# 20240925.net
KiCad netlist of a schematic drawn in Altium Designer
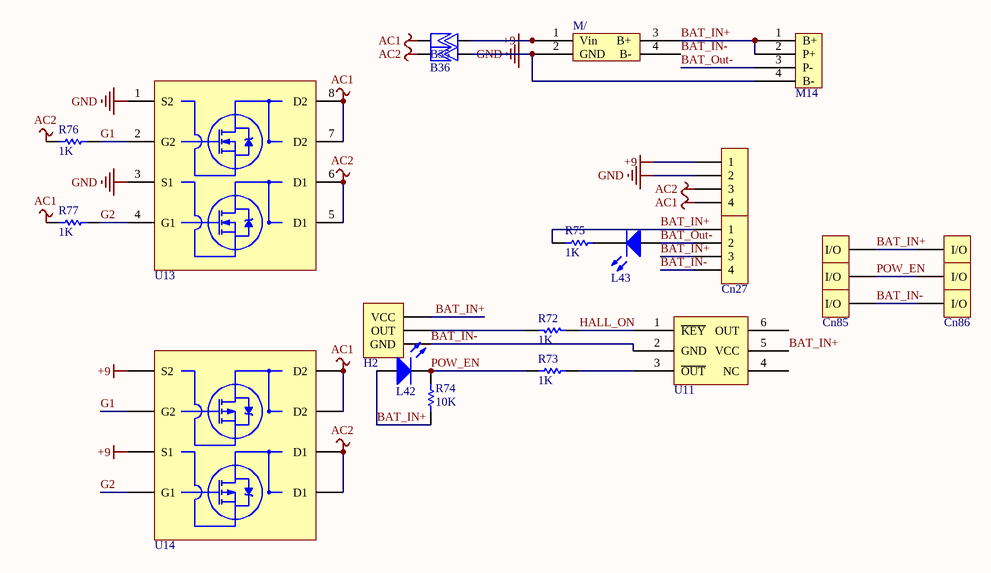
[diagram p0: 磁開關電路_20240925.SchDoc]

(export (version "E")
  (design (tool "Eeschema 10.0.6"))
  (components
    (comp (ref "B35")
      (value "短路")
      (footprint "BYPASS-1206")
      (description "短路焊點(如標註短路則需額外補錫使其短路)")
      (libsource (lib "MyLibray") (part "Bypass"))
    )
    (comp (ref "B36")
      (value "短路")
      (footprint "BYPASS-1206")
      (description "短路焊點(如標註短路則需額外補錫使其短路)")
      (libsource (lib "MyLibray") (part "Bypass"))
    )
    (comp (ref "Cn22")
      (value "KF2510-4")
      (footprint "Connector_KF2510-4W")
      (description "接線端子")
      (libsource (lib "MyLibray") (part "Contact(4P)"))
    )
    (comp (ref "Cn27")
      (value "KF2510-4")
      (footprint "Connector_KF2510-4W")
      (description "接線端子")
      (libsource (lib "MyLibray") (part "Contact(4P)"))
    )
    (comp (ref "Cn81")
      (value "Contact")
      (footprint "Contact_Joints1*0.5")
      (description "接線端子、接點、郵票孔(非焊接元件)")
      (libsource (lib "") (part "Contact_1"))
    )
    (comp (ref "Cn82")
      (value "Contact")
      (footprint "Contact_Joints1*0.5")
      (description "接線端子、接點、郵票孔(非焊接元件)")
      (libsource (lib "MyLibray") (part "Contact"))
    )
    (comp (ref "Cn83")
      (value "Contact")
      (footprint "Contact_Joints1*0.5")
      (description "接線端子、接點、郵票孔(非焊接元件)")
      (libsource (lib "") (part "Contact_1"))
    )
    (comp (ref "Cn84")
      (value "Contact")
      (footprint "Contact_Joints1*0.5")
      (description "接線端子、接點、郵票孔(非焊接元件)")
      (libsource (lib "MyLibray") (part "Contact"))
    )
    (comp (ref "Cn85")
      (value "Contact")
      (footprint "Contact_Joints1*0.5")
      (description "接線端子、接點、郵票孔(非焊接元件)")
      (libsource (lib "") (part "Contact_1"))
    )
    (comp (ref "Cn86")
      (value "Contact")
      (footprint "Contact_Joints1*0.5")
      (description "接線端子、接點、郵票孔(非焊接元件)")
      (libsource (lib "MyLibray") (part "Contact"))
    )
    (comp (ref "H2")
      (value "A3212")
      (footprint "SOT 23-3")
      (description "感測器_霍爾")
      (libsource (lib "MyLibray") (part "Sensor_Hall"))
    )
    (comp (ref "L42")
      (value "藍")
      (footprint "LED-1206")
      (description "LED")
      (libsource (lib "MyLibray") (part "LED"))
    )
    (comp (ref "L43")
      (value "藍")
      (footprint "LED-1206")
      (description "LED")
      (libsource (lib "MyLibray") (part "LED"))
    )
    (comp (ref "M/")
      (value "4056H+DW01A_Module")
      (footprint "4056H+DW01A_Module")
      (description "鋰電池充電保護板")
      (libsource (lib "MyLibray") (part "4056H+DW01A_Module"))
    )
    (comp (ref "M14")
      (value "Module_DW01A")
      (footprint "DW01A_Module")
      (description "鋰電池保護版")
      (libsource (lib "MyLibray") (part "Module_DW01A"))
    )
    (comp (ref "R72")
      (value "1K")
      (footprint "Res-1206")
      (description "電阻")
      (libsource (lib "MyLibray") (part "Res"))
    )
    (comp (ref "R73")
      (value "1K")
      (footprint "Res-1206")
      (description "電阻")
      (libsource (lib "MyLibray") (part "Res"))
    )
    (comp (ref "R74")
      (value "10K")
      (footprint "Res_1/4")
      (description "電阻")
      (libsource (lib "MyLibray") (part "Res"))
    )
    (comp (ref "R75")
      (value "1K")
      (footprint "Res-1206")
      (description "電阻")
      (libsource (lib "MyLibray") (part "Res"))
    )
    (comp (ref "R76")
      (value "1K")
      (footprint "Res-1206")
      (description "電阻")
      (libsource (lib "MyLibray") (part "Res"))
    )
    (comp (ref "R77")
      (value "1K")
      (footprint "Res-1206")
      (description "電阻")
      (libsource (lib "MyLibray") (part "Res"))
    )
    (comp (ref "U11")
      (value "CS2130")
      (footprint "SOT 23-6")
      (description "單鍵ON/OFF芯片")
      (libsource (lib "MyLibray") (part "CS2130"))
    )
    (comp (ref "U13")
      (value "AO4800")
      (footprint "SOP-8")
      (description "MOS,雙NMOS")
      (libsource (lib "MyLibray") (part "MOS_Dual N_AO4800"))
    )
    (comp (ref "U14")
      (value "AO4801")
      (footprint "SOP-8")
      (description "MOS,雙PMOS")
      (libsource (lib "MyLibray") (part "MOS_Dual P_AO4801"))
    )
  )
  (nets
    (net (code "1") (name "+9") (class "Default")
      (node (ref "B35") (pin "2") (pinfunction "2_2") (pintype "passive"))
      (node (ref "Cn22") (pin "1") (pinfunction "1_1") (pintype "passive"))
      (node (ref "M/") (pin "1") (pinfunction "Vin_1") (pintype "passive"))
      (node (ref "U14") (pin "1") (pinfunction "S2_1") (pintype "passive"))
      (node (ref "U14") (pin "3") (pinfunction "S1_3") (pintype "passive"))
    )
    (net (code "2") (name "/BAT_IN+") (class "Default")
      (node (ref "Cn27") (pin "1") (pinfunction "1_1") (pintype "passive"))
      (node (ref "Cn27") (pin "3") (pinfunction "3_3") (pintype "passive"))
      (node (ref "Cn81") (pin "1") (pinfunction "I/O_1") (pintype "passive"))
      (node (ref "Cn82") (pin "1") (pinfunction "I/O_1") (pintype "passive"))
      (node (ref "H2") (pin "1") (pinfunction "VCC_1") (pintype "power_in"))
      (node (ref "L42") (pin "2") (pinfunction "A_2") (pintype "passive"))
      (node (ref "M/") (pin "3") (pinfunction "B+_3") (pintype "passive"))
      (node (ref "M14") (pin "1") (pinfunction "B+_1") (pintype "passive"))
      (node (ref "M14") (pin "2") (pinfunction "P+_2") (pintype "passive"))
      (node (ref "R74") (pin "2") (pinfunction "2_2") (pintype "passive"))
      (node (ref "R75") (pin "2") (pinfunction "2_2") (pintype "passive"))
      (node (ref "U11") (pin "5") (pinfunction "VCC_5") (pintype "passive"))
    )
    (net (code "3") (name "/BAT_IN-") (class "Default")
      (node (ref "Cn27") (pin "4") (pinfunction "4_4") (pintype "passive"))
      (node (ref "Cn85") (pin "1") (pinfunction "I/O_1") (pintype "passive"))
      (node (ref "Cn86") (pin "1") (pinfunction "I/O_1") (pintype "passive"))
      (node (ref "H2") (pin "3") (pinfunction "GND_3") (pintype "power_in"))
      (node (ref "M/") (pin "4") (pinfunction "B-_4") (pintype "passive"))
      (node (ref "U11") (pin "2") (pinfunction "GND_2") (pintype "passive"))
    )
    (net (code "4") (name "/BAT_Out-") (class "Default")
      (node (ref "Cn27") (pin "2") (pinfunction "2_2") (pintype "passive"))
      (node (ref "L43") (pin "2") (pinfunction "A_2") (pintype "passive"))
      (node (ref "M14") (pin "3") (pinfunction "P-_3") (pintype "passive"))
    )
    (net (code "5") (name "/G1") (class "Default")
      (node (ref "R76") (pin "1") (pinfunction "1_1") (pintype "passive"))
      (node (ref "U13") (pin "2") (pinfunction "G2_2") (pintype "passive"))
      (node (ref "U14") (pin "2") (pinfunction "G2_2") (pintype "passive"))
    )
    (net (code "6") (name "/G2") (class "Default")
      (node (ref "R77") (pin "1") (pinfunction "1_1") (pintype "passive"))
      (node (ref "U13") (pin "4") (pinfunction "G1_4") (pintype "passive"))
      (node (ref "U14") (pin "4") (pinfunction "G1_4") (pintype "passive"))
    )
    (net (code "7") (name "/HALL_ON") (class "Default")
      (node (ref "R72") (pin "1") (pinfunction "1_1") (pintype "passive"))
      (node (ref "U11") (pin "1") (pinfunction "~{KEY}_1") (pintype "passive"))
    )
    (net (code "8") (name "/POW_EN") (class "Default")
      (node (ref "Cn83") (pin "1") (pinfunction "I/O_1") (pintype "passive"))
      (node (ref "Cn84") (pin "1") (pinfunction "I/O_1") (pintype "passive"))
      (node (ref "L42") (pin "1") (pinfunction "K_1") (pintype "passive"))
      (node (ref "R73") (pin "1") (pinfunction "1_1") (pintype "passive"))
      (node (ref "R74") (pin "1") (pinfunction "1_1") (pintype "passive"))
    )
    (net (code "9") (name "AC1") (class "Default")
      (node (ref "B35") (pin "1") (pinfunction "1_1") (pintype "passive"))
      (node (ref "Cn22") (pin "4") (pinfunction "4_4") (pintype "passive"))
      (node (ref "R77") (pin "2") (pinfunction "2_2") (pintype "passive"))
      (node (ref "U13") (pin "7") (pinfunction "D2_7") (pintype "passive"))
      (node (ref "U13") (pin "8") (pinfunction "D2_8") (pintype "passive"))
      (node (ref "U14") (pin "7") (pinfunction "D2_7") (pintype "passive"))
      (node (ref "U14") (pin "8") (pinfunction "D2_8") (pintype "passive"))
    )
    (net (code "10") (name "AC2") (class "Default")
      (node (ref "B36") (pin "1") (pinfunction "1_1") (pintype "passive"))
      (node (ref "Cn22") (pin "3") (pinfunction "3_3") (pintype "passive"))
      (node (ref "R76") (pin "2") (pinfunction "2_2") (pintype "passive"))
      (node (ref "U13") (pin "5") (pinfunction "D1_5") (pintype "passive"))
      (node (ref "U13") (pin "6") (pinfunction "D1_6") (pintype "passive"))
      (node (ref "U14") (pin "5") (pinfunction "D1_5") (pintype "passive"))
      (node (ref "U14") (pin "6") (pinfunction "D1_6") (pintype "passive"))
    )
    (net (code "11") (name "GND") (class "Default")
      (node (ref "B36") (pin "2") (pinfunction "2_2") (pintype "passive"))
      (node (ref "Cn22") (pin "2") (pinfunction "2_2") (pintype "passive"))
      (node (ref "M/") (pin "2") (pinfunction "GND_2") (pintype "passive"))
      (node (ref "M14") (pin "4") (pinfunction "B-_4") (pintype "passive"))
      (node (ref "U13") (pin "1") (pinfunction "S2_1") (pintype "passive"))
      (node (ref "U13") (pin "3") (pinfunction "S1_3") (pintype "passive"))
    )
    (net (code "12") (name "Net-(H2-OUT)") (class "Default")
      (node (ref "H2") (pin "2") (pinfunction "OUT_2") (pintype "power_in"))
      (node (ref "R72") (pin "2") (pinfunction "2_2") (pintype "passive"))
    )
    (net (code "13") (name "Net-(L43-K)") (class "Default")
      (node (ref "L43") (pin "1") (pinfunction "K_1") (pintype "passive"))
      (node (ref "R75") (pin "1") (pinfunction "1_1") (pintype "passive"))
    )
    (net (code "14") (name "Net-(U11-~{OUT})") (class "Default")
      (node (ref "R73") (pin "2") (pinfunction "2_2") (pintype "passive"))
      (node (ref "U11") (pin "3") (pinfunction "~{OUT}_3") (pintype "passive"))
    )
    (net (code "15") (name "unconnected-(U11-NC-Pad4)") (class "Default")
      (node (ref "U11") (pin "4") (pinfunction "NC_4") (pintype "passive"))
    )
    (net (code "16") (name "unconnected-(U11-OUT-Pad6)") (class "Default")
      (node (ref "U11") (pin "6") (pinfunction "OUT_6") (pintype "passive"))
    )
  )
)
